# 3_USB_TO_UART.net
KiCad netlist of a schematic drawn in Altium Designer
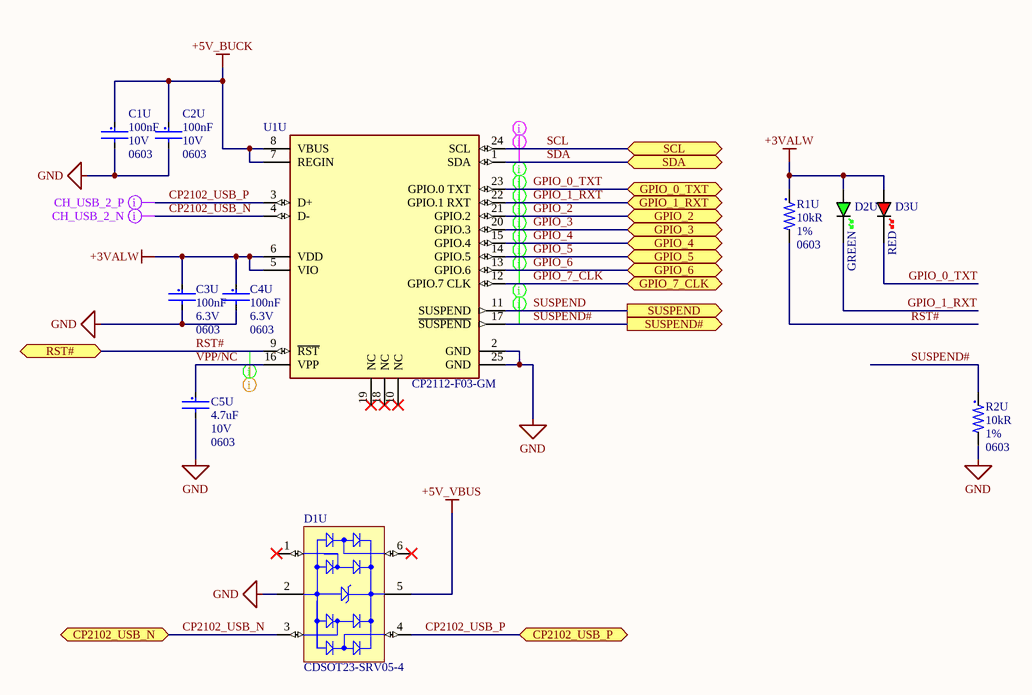
[diagram p0: 3_USB_TO_UART.SchDoc]

(export (version "E")
  (design (tool "Eeschema 10.0.6"))
  (components
    (comp (ref "C1U")
      (value "100nF")
      (footprint "C0603-IPC_C_No_Silk")
      (description "Multilayer Ceramic Capacitor, 0.1 uF, 10 V, ± 10%, X7R, 0603 [1608 Metric]")
      (fields
        (field (name "MANUFACTURER") "KEMET")
        (field (name "MANUFACTURER PART NUMBER") "C0603C104K8RACTU")
        (field (name "VOLTAGE RATING (DC)") "10V")
        (field (name "CASE/PACKAGE") "0603")
      )
      (libsource (lib "Lib_Capacitor_0603") (part "100nF_10V"))
    )
    (comp (ref "C2U")
      (value "100nF")
      (footprint "C0603-IPC_C_No_Silk")
      (description "Multilayer Ceramic Capacitor, 0.1 uF, 10 V, ± 10%, X7R, 0603 [1608 Metric]")
      (fields
        (field (name "MANUFACTURER") "KEMET")
        (field (name "MANUFACTURER PART NUMBER") "C0603C104K8RACTU")
        (field (name "VOLTAGE RATING (DC)") "10V")
        (field (name "CASE/PACKAGE") "0603")
      )
      (libsource (lib "Lib_Capacitor_0603") (part "100nF_10V"))
    )
    (comp (ref "C3U")
      (value "100nF")
      (footprint "C0603-IPC_C_No_Silk")
      (description "Cap Cer 0.1UF 6.3V X7R 0603")
      (fields
        (field (name "MANUFACTURER") "KYOCERA AVX")
        (field (name "MANUFACTURER PART NUMBER") "KGM15AR70J104KM")
        (field (name "VOLTAGE") "6.3V")
        (field (name "PACKAGE") "0603")
      )
      (libsource (lib "Lib_Capacitor_0603") (part "100nF_6.3V"))
    )
    (comp (ref "C4U")
      (value "100nF")
      (footprint "C0603-IPC_C_No_Silk")
      (description "Cap Cer 0.1UF 6.3V X7R 0603")
      (fields
        (field (name "MANUFACTURER") "KYOCERA AVX")
        (field (name "MANUFACTURER PART NUMBER") "KGM15AR70J104KM")
        (field (name "VOLTAGE") "6.3V")
        (field (name "PACKAGE") "0603")
      )
      (libsource (lib "Lib_Capacitor_0603") (part "100nF_6.3V"))
    )
    (comp (ref "C5U")
      (value "4.7uF")
      (footprint "C0603-MFG_No_Silk")
      (description "Multilayer Ceramic Capacitor, 4.7 uF, 10 V, ± 10%, X5R, 0603 [1608 Metric]")
      (fields
        (field (name "MANUFACTURER") "Samsung")
        (field (name "MANUFACTURER PART NUMBER") "CL10A475KP8NNNC")
        (field (name "VOLTAGE RATING (DC)") "10V")
        (field (name "CASE/PACKAGE") "0603")
      )
      (libsource (lib "Lib_Capacitor_0603") (part "4.7uF_10V"))
    )
    (comp (ref "D1U")
      (value "CDSOT23-SRV05-4")
      (footprint "SOT23-6-IPC_C")
      (description "TVS DIODE 5V 15V SOT23-6")
      (fields
        (field (name "MANUFACTURER") "Bourns Inc.")
        (field (name "OCTOPART") "https://octopart.com/cdsot23-srv05-4-bourns-1679449")
      )
      (libsource (lib "Lib_IC_ESD") (part "SRV05-4"))
    )
    (comp (ref "D2U")
      (value "GREEN")
      (footprint "LED_0603_GREEN")
      (description "LED 0603 GREEN SMD")
      (libsource (lib "Lib_LED") (part "LED_0603_GREEN"))
    )
    (comp (ref "D3U")
      (value "RED")
      (footprint "LED_0603_RED")
      (description "LED 0603 RED SMD")
      (libsource (lib "Lib_LED") (part "LED_0603_RED"))
    )
    (comp (ref "R1U")
      (value "10kR")
      (footprint "R0603-MFG")
      (description "SMD Chip Resistor, 10 kOhm, ± 1%, 100 mW, 0603 [1608 Metric], Thick Film, General Purpose")
      (fields
        (field (name "MANUFACTURER") "Yageo")
        (field (name "MANUFACTURER PART NUMBER") "RC0603FR-0710KL")
        (field (name "TOLERANCE") "1%")
        (field (name "CASE/PACKAGE") "0603")
      )
      (libsource (lib "Lib_Register_0603") (part "10K"))
    )
    (comp (ref "R2U")
      (value "10kR")
      (footprint "R0603-MFG")
      (description "SMD Chip Resistor, 10 kOhm, ± 1%, 100 mW, 0603 [1608 Metric], Thick Film, General Purpose")
      (fields
        (field (name "MANUFACTURER") "Yageo")
        (field (name "MANUFACTURER PART NUMBER") "RC0603FR-0710KL")
        (field (name "TOLERANCE") "1%")
        (field (name "CASE/PACKAGE") "0603")
      )
      (libsource (lib "Lib_Register_0603") (part "10K"))
    )
    (comp (ref "U1U")
      (value "CP2112-F03-GM")
      (footprint "CP2112-IPC_A")
      (description "IC HID USB-TO-SMBUS BRIDGE 24QFN")
      (fields
        (field (name "MANUFACTURER") "Silicon Labs")
        (field (name "OCTOPART") "https://octopart.com/cp2112-f03-gm-silicon+labs-81780828")
      )
      (libsource (lib "Lib_IC_UART") (part "CP2112-F03-GM"))
    )
  )
  (nets
    (net (code "1") (name "+3VALW") (class "Default")
      (node (ref "C3U") (pin "1") (pinfunction "1_1") (pintype "passive"))
      (node (ref "C4U") (pin "1") (pinfunction "1_1") (pintype "passive"))
      (node (ref "D2U") (pin "2") (pinfunction "A_2") (pintype "passive"))
      (node (ref "D3U") (pin "2") (pinfunction "A_2") (pintype "passive"))
      (node (ref "R1U") (pin "1") (pinfunction "1_1") (pintype "passive"))
      (node (ref "U1U") (pin "5") (pinfunction "VIO_5") (pintype "power_in"))
      (node (ref "U1U") (pin "6") (pinfunction "VDD_6") (pintype "power_in"))
    )
    (net (code "2") (name "+5V_BUCK") (class "Default")
      (node (ref "C1U") (pin "1") (pinfunction "1_1") (pintype "passive"))
      (node (ref "C2U") (pin "1") (pinfunction "1_1") (pintype "passive"))
      (node (ref "U1U") (pin "7") (pinfunction "REGIN_7") (pintype "power_in"))
      (node (ref "U1U") (pin "8") (pinfunction "VBUS_8") (pintype "power_in"))
    )
    (net (code "3") (name "+5V_VBUS") (class "Default")
      (node (ref "D1U") (pin "5") (pinfunction "VBUS_5") (pintype "power_in"))
    )
    (net (code "4") (name "/CP2102_USB_N") (class "Default")
      (node (ref "D1U") (pin "3") (pinfunction "I/O_2_3") (pintype "bidirectional"))
      (node (ref "U1U") (pin "4") (pinfunction "D-_4") (pintype "bidirectional"))
    )
    (net (code "5") (name "/CP2102_USB_P") (class "Default")
      (node (ref "D1U") (pin "4") (pinfunction "I/O_3_4") (pintype "bidirectional"))
      (node (ref "U1U") (pin "3") (pinfunction "D+_3") (pintype "bidirectional"))
    )
    (net (code "6") (name "/GPIO_0_TXT") (class "Default")
      (node (ref "D3U") (pin "1") (pinfunction "K_1") (pintype "passive"))
      (node (ref "U1U") (pin "23") (pinfunction "GPIO.0_TXT_23") (pintype "bidirectional"))
    )
    (net (code "7") (name "/GPIO_1_RXT") (class "Default")
      (node (ref "D2U") (pin "1") (pinfunction "K_1") (pintype "passive"))
      (node (ref "U1U") (pin "22") (pinfunction "GPIO.1_RXT_22") (pintype "bidirectional"))
    )
    (net (code "8") (name "/GPIO_2") (class "Default")
      (node (ref "U1U") (pin "21") (pinfunction "GPIO.2_21") (pintype "bidirectional"))
    )
    (net (code "9") (name "/GPIO_3") (class "Default")
      (node (ref "U1U") (pin "20") (pinfunction "GPIO.3_20") (pintype "bidirectional"))
    )
    (net (code "10") (name "/GPIO_4") (class "Default")
      (node (ref "U1U") (pin "15") (pinfunction "GPIO.4_15") (pintype "bidirectional"))
    )
    (net (code "11") (name "/GPIO_5") (class "Default")
      (node (ref "U1U") (pin "14") (pinfunction "GPIO.5_14") (pintype "bidirectional"))
    )
    (net (code "12") (name "/GPIO_6") (class "Default")
      (node (ref "U1U") (pin "13") (pinfunction "GPIO.6_13") (pintype "bidirectional"))
    )
    (net (code "13") (name "/GPIO_7_CLK") (class "Default")
      (node (ref "U1U") (pin "12") (pinfunction "GPIO.7_CLK_12") (pintype "bidirectional"))
    )
    (net (code "14") (name "/RST#") (class "Default")
      (node (ref "R1U") (pin "2") (pinfunction "2_2") (pintype "passive"))
      (node (ref "U1U") (pin "9") (pinfunction "~{RST}_9") (pintype "bidirectional"))
    )
    (net (code "15") (name "/SCL") (class "Default")
      (node (ref "U1U") (pin "24") (pinfunction "SCL_24") (pintype "bidirectional"))
    )
    (net (code "16") (name "/SDA") (class "Default")
      (node (ref "U1U") (pin "1") (pinfunction "SDA_1") (pintype "bidirectional"))
    )
    (net (code "17") (name "/SUSPEND") (class "Default")
      (node (ref "U1U") (pin "11") (pinfunction "SUSPEND_11") (pintype "output"))
    )
    (net (code "18") (name "/SUSPEND#") (class "Default")
      (node (ref "R2U") (pin "1") (pinfunction "1_1") (pintype "passive"))
      (node (ref "U1U") (pin "17") (pinfunction "~{SUSPEND}_17") (pintype "output"))
    )
    (net (code "19") (name "/VPP{slash}NC") (class "Default")
      (node (ref "C5U") (pin "1") (pinfunction "1_1") (pintype "passive"))
      (node (ref "U1U") (pin "16") (pinfunction "VPP_16") (pintype "power_in"))
    )
    (net (code "20") (name "GND") (class "Default")
      (node (ref "C1U") (pin "2") (pinfunction "2_2") (pintype "passive"))
      (node (ref "C2U") (pin "2") (pinfunction "2_2") (pintype "passive"))
      (node (ref "C3U") (pin "2") (pinfunction "2_2") (pintype "passive"))
      (node (ref "C4U") (pin "2") (pinfunction "2_2") (pintype "passive"))
      (node (ref "C5U") (pin "2") (pinfunction "2_2") (pintype "passive"))
      (node (ref "D1U") (pin "2") (pinfunction "GND_2") (pintype "power_in"))
      (node (ref "R2U") (pin "2") (pinfunction "2_2") (pintype "passive"))
      (node (ref "U1U") (pin "2") (pinfunction "GND_2") (pintype "power_in"))
      (node (ref "U1U") (pin "25") (pinfunction "GND_25") (pintype "power_in"))
    )
    (net (code "21") (name "unconnected-(D1U-I{slash}O_1-Pad1)") (class "Default")
      (node (ref "D1U") (pin "1") (pinfunction "I/O_1_1") (pintype "bidirectional+no_connect"))
    )
    (net (code "22") (name "unconnected-(D1U-I{slash}O_4-Pad6)") (class "Default")
      (node (ref "D1U") (pin "6") (pinfunction "I/O_4_6") (pintype "bidirectional+no_connect"))
    )
    (net (code "23") (name "unconnected-(U1U-NC-Pad10)") (class "Default")
      (node (ref "U1U") (pin "10") (pinfunction "NC_10") (pintype "passive+no_connect"))
    )
    (net (code "24") (name "unconnected-(U1U-NC-Pad18)") (class "Default")
      (node (ref "U1U") (pin "18") (pinfunction "NC_18") (pintype "passive+no_connect"))
    )
    (net (code "25") (name "unconnected-(U1U-NC-Pad19)") (class "Default")
      (node (ref "U1U") (pin "19") (pinfunction "NC_19") (pintype "passive+no_connect"))
    )
  )
)
